# schaltplan.net
KiCad netlist of a schematic drawn in EAGLE
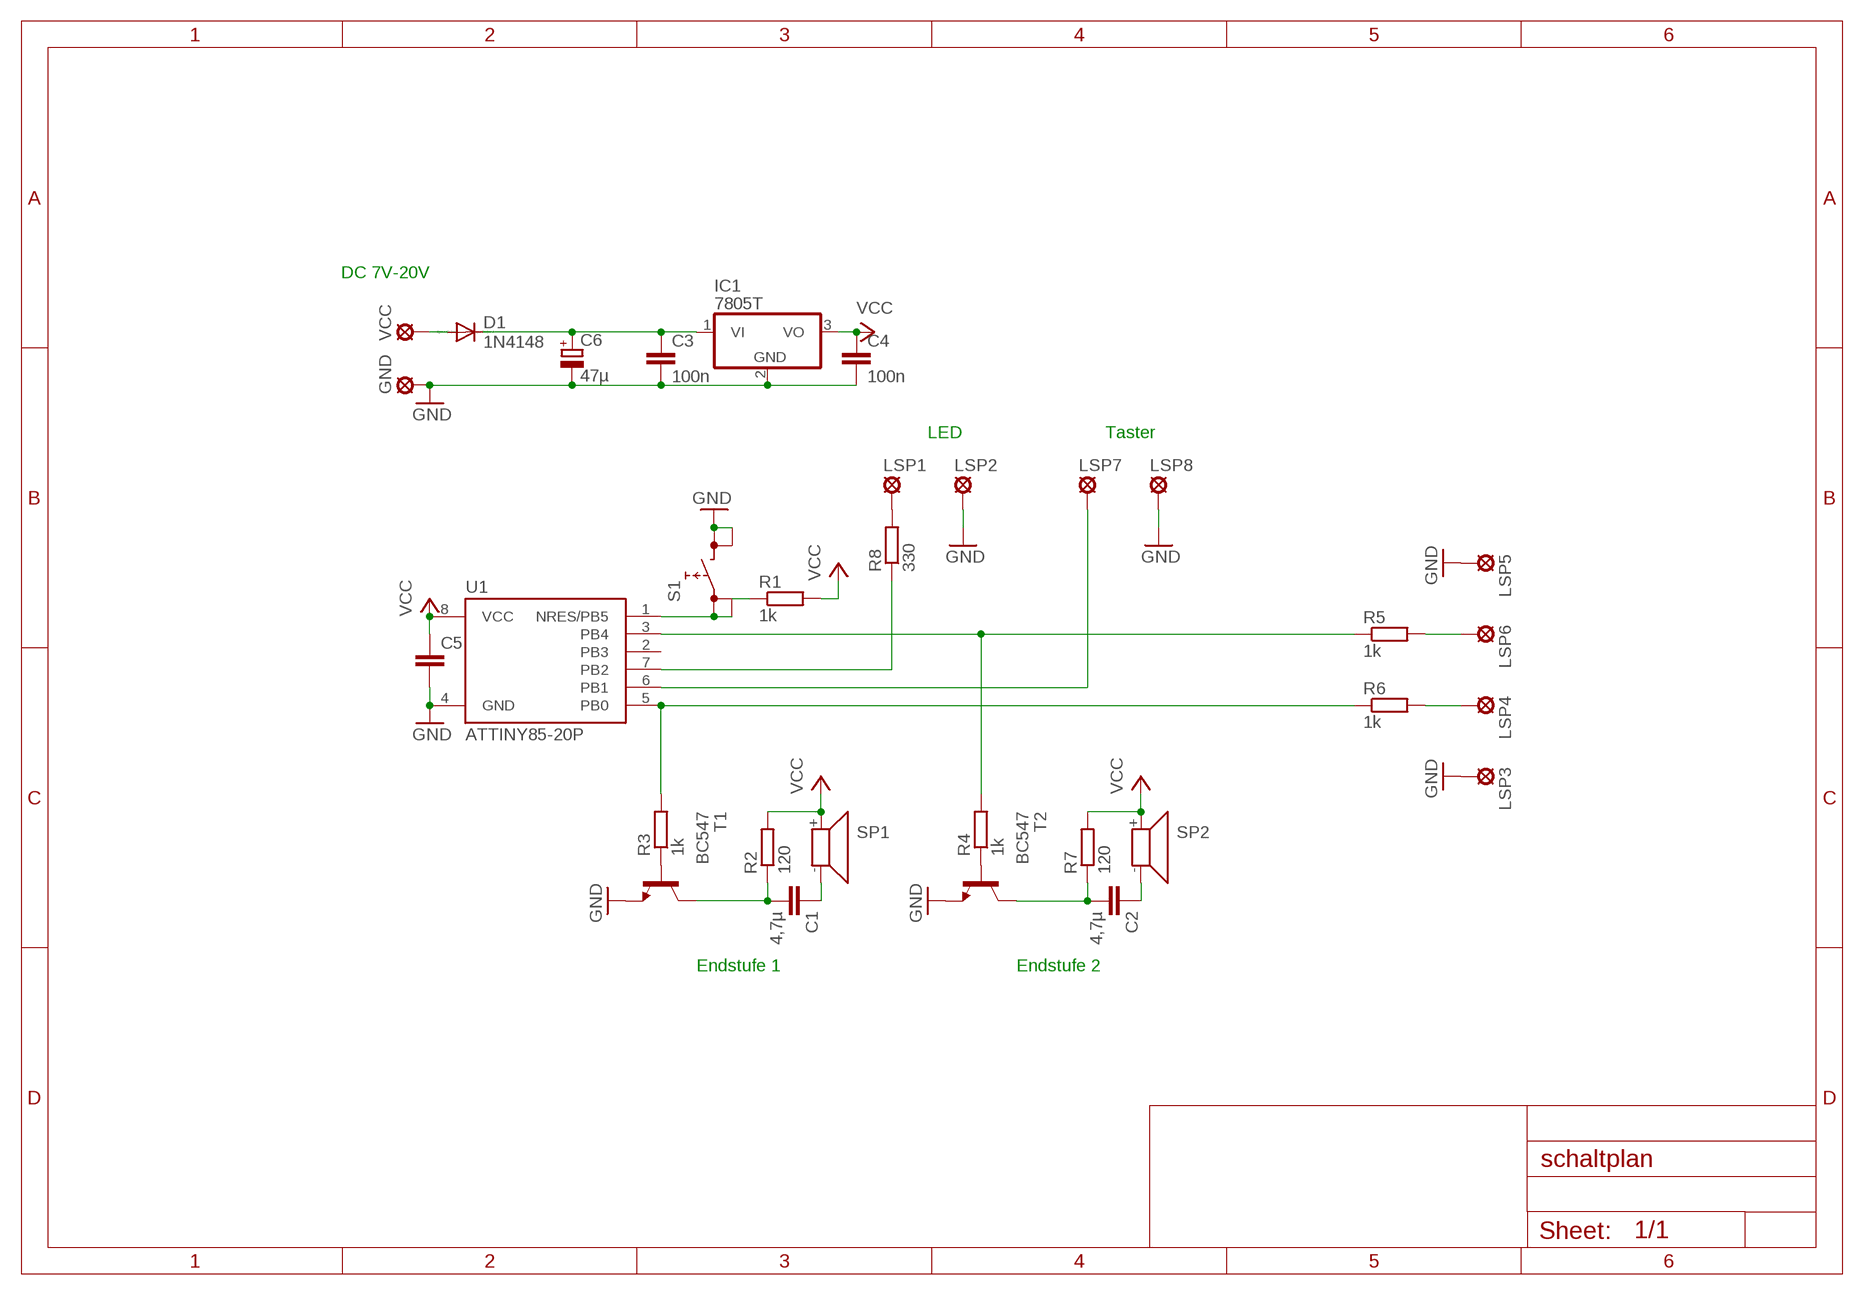
[diagram p0: schematic, sheet 1]

(export (version "E")
  (design (tool "Eeschema 10.0.6"))
  (components
    (comp (ref "C1")
      (value "4,7µ")
      (footprint "eagle-import:C5B3")
      (libsource (lib "eagle-import") (part "C5/3"))
    )
    (comp (ref "C2")
      (value "4,7µ")
      (footprint "eagle-import:C5B3")
      (libsource (lib "eagle-import") (part "C5/3"))
    )
    (comp (ref "C3")
      (value "100n")
      (footprint "eagle-import:C5B3")
      (libsource (lib "eagle-import") (part "C5/3"))
    )
    (comp (ref "C4")
      (value "100n")
      (footprint "eagle-import:C5B3")
      (libsource (lib "eagle-import") (part "C5/3"))
    )
    (comp (ref "C5")
      (value "C5/3")
      (footprint "eagle-import:C5B3")
      (libsource (lib "eagle-import") (part "C5/3"))
    )
    (comp (ref "C6")
      (value "47µ")
      (footprint "eagle-import:A_3216-18W")
      (libsource (lib "eagle-import") (part "CPOL-EUA/3216-18W"))
    )
    (comp (ref "D1")
      (value "1N4148")
      (footprint "eagle-import:D-12.5")
      (libsource (lib "eagle-import") (part "DIODE-D-12.5"))
    )
    (comp (ref "GND")
      (value "LSP10")
      (footprint "eagle-import:LSP10")
      (libsource (lib "eagle-import") (part "LSP10"))
    )
    (comp (ref "IC1")
      (value "7805T")
      (footprint "eagle-import:TO220H")
      (libsource (lib "eagle-import") (part "78T05"))
    )
    (comp (ref "LSP1")
      (value "LSP10")
      (footprint "eagle-import:LSP10")
      (libsource (lib "eagle-import") (part "LSP10"))
    )
    (comp (ref "LSP2")
      (value "LSP10")
      (footprint "eagle-import:LSP10")
      (libsource (lib "eagle-import") (part "LSP10"))
    )
    (comp (ref "LSP3")
      (value "LSP10")
      (footprint "eagle-import:LSP10")
      (libsource (lib "eagle-import") (part "LSP10"))
    )
    (comp (ref "LSP4")
      (value "LSP10")
      (footprint "eagle-import:LSP10")
      (libsource (lib "eagle-import") (part "LSP10"))
    )
    (comp (ref "LSP5")
      (value "LSP10")
      (footprint "eagle-import:LSP10")
      (libsource (lib "eagle-import") (part "LSP10"))
    )
    (comp (ref "LSP6")
      (value "LSP10")
      (footprint "eagle-import:LSP10")
      (libsource (lib "eagle-import") (part "LSP10"))
    )
    (comp (ref "LSP7")
      (value "LSP10")
      (footprint "eagle-import:LSP10")
      (libsource (lib "eagle-import") (part "LSP10"))
    )
    (comp (ref "LSP8")
      (value "LSP10")
      (footprint "eagle-import:LSP10")
      (libsource (lib "eagle-import") (part "LSP10"))
    )
    (comp (ref "R1")
      (value "1k")
      (footprint "eagle-import:0204_7")
      (libsource (lib "eagle-import") (part "R-EU_0204/7"))
    )
    (comp (ref "R2")
      (value "120")
      (footprint "eagle-import:0204_7")
      (libsource (lib "eagle-import") (part "R-EU_0204/7"))
    )
    (comp (ref "R3")
      (value "1k")
      (footprint "eagle-import:0204_7")
      (libsource (lib "eagle-import") (part "R-EU_0204/7"))
    )
    (comp (ref "R4")
      (value "1k")
      (footprint "eagle-import:0204_7")
      (libsource (lib "eagle-import") (part "R-EU_0204/7"))
    )
    (comp (ref "R5")
      (value "1k")
      (footprint "eagle-import:0204_7")
      (libsource (lib "eagle-import") (part "R-EU_0204/7"))
    )
    (comp (ref "R6")
      (value "1k")
      (footprint "eagle-import:0204_7")
      (libsource (lib "eagle-import") (part "R-EU_0204/7"))
    )
    (comp (ref "R7")
      (value "120")
      (footprint "eagle-import:0204_7")
      (libsource (lib "eagle-import") (part "R-EU_0204/7"))
    )
    (comp (ref "R8")
      (value "330")
      (footprint "eagle-import:0204_7")
      (libsource (lib "eagle-import") (part "R-EU_0204/7"))
    )
    (comp (ref "S1")
      (value "REKN")
      (footprint "eagle-import:REKN")
      (libsource (lib "eagle-import") (part "REKN"))
    )
    (comp (ref "SP1")
      (value "SMS-1308MS-2-R")
      (footprint "eagle-import:SMS-1308MS-2-R")
      (libsource (lib "eagle-import") (part "SMS-1308MS-2-R"))
    )
    (comp (ref "SP2")
      (value "SMS-1308MS-2-R")
      (footprint "eagle-import:SMS-1308MS-2-R")
      (libsource (lib "eagle-import") (part "SMS-1308MS-2-R"))
    )
    (comp (ref "T1")
      (value "BC547")
      (footprint "eagle-import:TO92")
      (libsource (lib "eagle-import") (part "BC547"))
    )
    (comp (ref "T2")
      (value "BC547")
      (footprint "eagle-import:TO92")
      (libsource (lib "eagle-import") (part "BC547"))
    )
    (comp (ref "U1")
      (value "ATTINY85-20P")
      (footprint "eagle-import:PDIP08_300MIL")
      (libsource (lib "eagle-import") (part "ATTINY85P-20"))
    )
    (comp (ref "VCC")
      (value "LSP10")
      (footprint "eagle-import:LSP10")
      (libsource (lib "eagle-import") (part "LSP10"))
    )
  )
  (nets
    (net (code "1") (name "GND") (class "Default")
      (node (ref "C3") (pin "2") (pinfunction "2_2") (pintype "passive"))
      (node (ref "C4") (pin "2") (pinfunction "2_2") (pintype "passive"))
      (node (ref "C5") (pin "2") (pinfunction "2_2") (pintype "passive"))
      (node (ref "C6") (pin "-") (pinfunction "-_-") (pintype "passive"))
      (node (ref "GND") (pin "MP") (pinfunction "MP_MP") (pintype "passive"))
      (node (ref "IC1") (pin "2") (pinfunction "GND_2") (pintype "passive"))
      (node (ref "LSP2") (pin "MP") (pinfunction "MP_MP") (pintype "passive"))
      (node (ref "LSP3") (pin "MP") (pinfunction "MP_MP") (pintype "passive"))
      (node (ref "LSP5") (pin "MP") (pinfunction "MP_MP") (pintype "passive"))
      (node (ref "LSP8") (pin "MP") (pinfunction "MP_MP") (pintype "passive"))
      (node (ref "S1") (pin "1A") (pinfunction "1_1A") (pintype "passive"))
      (node (ref "S1") (pin "1B") (pinfunction "1_1B") (pintype "passive"))
      (node (ref "T1") (pin "1") (pinfunction "E_1") (pintype "passive"))
      (node (ref "T2") (pin "1") (pinfunction "E_1") (pintype "passive"))
      (node (ref "U1") (pin "4") (pinfunction "GND_4") (pintype "power_in"))
    )
    (net (code "2") (name "Net-(D1-PadA)") (class "Default")
      (node (ref "D1") (pin "A") (pinfunction "A_A") (pintype "passive"))
      (node (ref "VCC") (pin "MP") (pinfunction "MP_MP") (pintype "passive"))
    )
    (net (code "3") (name "Net-(IC1-VI)") (class "Default")
      (node (ref "C3") (pin "1") (pinfunction "1_1") (pintype "passive"))
      (node (ref "C6") (pin "+") (pinfunction "+_+") (pintype "passive"))
      (node (ref "D1") (pin "C") (pinfunction "C_C") (pintype "passive"))
      (node (ref "IC1") (pin "1") (pinfunction "VI_1") (pintype "input"))
    )
    (net (code "4") (name "Net-(LSP1-PadMP)") (class "Default")
      (node (ref "LSP1") (pin "MP") (pinfunction "MP_MP") (pintype "passive"))
      (node (ref "R8") (pin "2") (pinfunction "2_2") (pintype "passive"))
    )
    (net (code "5") (name "Net-(LSP4-PadMP)") (class "Default")
      (node (ref "LSP4") (pin "MP") (pinfunction "MP_MP") (pintype "passive"))
      (node (ref "R6") (pin "2") (pinfunction "2_2") (pintype "passive"))
    )
    (net (code "6") (name "Net-(LSP6-PadMP)") (class "Default")
      (node (ref "LSP6") (pin "MP") (pinfunction "MP_MP") (pintype "passive"))
      (node (ref "R5") (pin "2") (pinfunction "2_2") (pintype "passive"))
    )
    (net (code "7") (name "Net-(SP1-2)") (class "Default")
      (node (ref "C1") (pin "1") (pinfunction "1_1") (pintype "passive"))
      (node (ref "SP1") (pin "-") (pinfunction "2_-") (pintype "passive"))
    )
    (net (code "8") (name "Net-(SP2-2)") (class "Default")
      (node (ref "C2") (pin "1") (pinfunction "1_1") (pintype "passive"))
      (node (ref "SP2") (pin "-") (pinfunction "2_-") (pintype "passive"))
    )
    (net (code "9") (name "Net-(T1-B)") (class "Default")
      (node (ref "R3") (pin "1") (pinfunction "1_1") (pintype "passive"))
      (node (ref "T1") (pin "2") (pinfunction "B_2") (pintype "passive"))
    )
    (net (code "10") (name "Net-(T1-C)") (class "Default")
      (node (ref "C1") (pin "2") (pinfunction "2_2") (pintype "passive"))
      (node (ref "R2") (pin "1") (pinfunction "1_1") (pintype "passive"))
      (node (ref "T1") (pin "3") (pinfunction "C_3") (pintype "passive"))
    )
    (net (code "11") (name "Net-(T2-B)") (class "Default")
      (node (ref "R4") (pin "1") (pinfunction "1_1") (pintype "passive"))
      (node (ref "T2") (pin "2") (pinfunction "B_2") (pintype "passive"))
    )
    (net (code "12") (name "Net-(T2-C)") (class "Default")
      (node (ref "C2") (pin "2") (pinfunction "2_2") (pintype "passive"))
      (node (ref "R7") (pin "1") (pinfunction "1_1") (pintype "passive"))
      (node (ref "T2") (pin "3") (pinfunction "C_3") (pintype "passive"))
    )
    (net (code "13") (name "Net-(U1-NRES{slash}PB5)") (class "Default")
      (node (ref "S1") (pin "0A") (pinfunction "0_0A") (pintype "passive"))
      (node (ref "S1") (pin "0B") (pinfunction "0_0B") (pintype "passive"))
      (node (ref "U1") (pin "1") (pinfunction "NRES/PB5_1") (pintype "bidirectional"))
    )
    (net (code "14") (name "Net-(U1-PB0)") (class "Default")
      (node (ref "R3") (pin "2") (pinfunction "2_2") (pintype "passive"))
      (node (ref "R6") (pin "1") (pinfunction "1_1") (pintype "passive"))
      (node (ref "U1") (pin "5") (pinfunction "PB0_5") (pintype "bidirectional"))
    )
    (net (code "15") (name "Net-(U1-PB1)") (class "Default")
      (node (ref "LSP7") (pin "MP") (pinfunction "MP_MP") (pintype "passive"))
      (node (ref "U1") (pin "6") (pinfunction "PB1_6") (pintype "bidirectional"))
    )
    (net (code "16") (name "Net-(U1-PB2)") (class "Default")
      (node (ref "R8") (pin "1") (pinfunction "1_1") (pintype "passive"))
      (node (ref "U1") (pin "7") (pinfunction "PB2_7") (pintype "bidirectional"))
    )
    (net (code "17") (name "Net-(U1-PB4)") (class "Default")
      (node (ref "R4") (pin "2") (pinfunction "2_2") (pintype "passive"))
      (node (ref "R5") (pin "1") (pinfunction "1_1") (pintype "passive"))
      (node (ref "U1") (pin "3") (pinfunction "PB4_3") (pintype "bidirectional"))
    )
    (net (code "18") (name "VCC") (class "Default")
      (node (ref "C4") (pin "1") (pinfunction "1_1") (pintype "passive"))
      (node (ref "C5") (pin "1") (pinfunction "1_1") (pintype "passive"))
      (node (ref "IC1") (pin "3") (pinfunction "VO_3") (pintype "passive"))
      (node (ref "R1") (pin "2") (pinfunction "2_2") (pintype "passive"))
      (node (ref "R2") (pin "2") (pinfunction "2_2") (pintype "passive"))
      (node (ref "R7") (pin "2") (pinfunction "2_2") (pintype "passive"))
      (node (ref "SP1") (pin "+") (pinfunction "1_+") (pintype "passive"))
      (node (ref "SP2") (pin "+") (pinfunction "1_+") (pintype "passive"))
      (node (ref "U1") (pin "8") (pinfunction "VCC_8") (pintype "power_in"))
    )
    (net (code "19") (name "unconnected-(R1-Pad1)") (class "Default")
      (node (ref "R1") (pin "1") (pinfunction "1_1") (pintype "passive"))
    )
    (net (code "20") (name "unconnected-(U1-PB3-Pad2)") (class "Default")
      (node (ref "U1") (pin "2") (pinfunction "PB3_2") (pintype "bidirectional"))
    )
  )
)
